# USB_Host.net
KiCad netlist of a schematic drawn in EAGLE
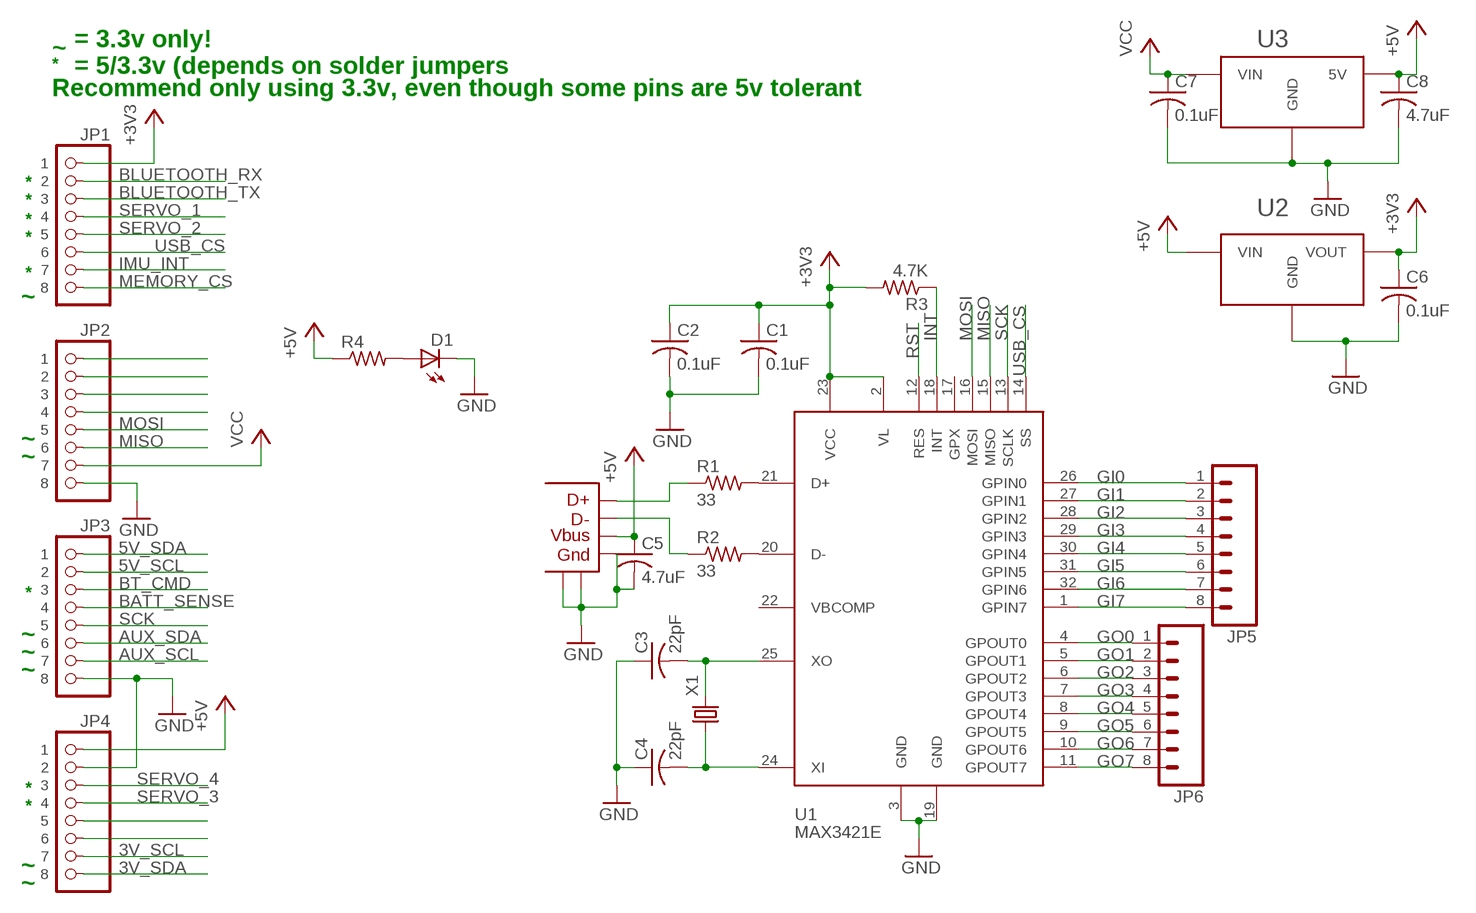
[diagram p0: schematic, sheet 1]

(export (version "E")
  (design (tool "Eeschema 10.0.6"))
  (components
    (comp (ref "C1")
      (value "0.1uF")
      (footprint "eagle-import:C0603")
      (libsource (lib "eagle-import") (part "C-USC0603"))
    )
    (comp (ref "C2")
      (value "0.1uF")
      (footprint "eagle-import:C0603")
      (libsource (lib "eagle-import") (part "C-USC0603"))
    )
    (comp (ref "C3")
      (value "22pF")
      (footprint "eagle-import:C0603")
      (libsource (lib "eagle-import") (part "C-USC0603"))
    )
    (comp (ref "C4")
      (value "22pF")
      (footprint "eagle-import:C0603")
      (libsource (lib "eagle-import") (part "C-USC0603"))
    )
    (comp (ref "C5")
      (value "4.7uF")
      (footprint "eagle-import:C0603")
      (libsource (lib "eagle-import") (part "C-USC0603"))
    )
    (comp (ref "C6")
      (value "0.1uF")
      (footprint "eagle-import:C0603")
      (libsource (lib "eagle-import") (part "C-USC0603"))
    )
    (comp (ref "C7")
      (value "0.1uF")
      (footprint "eagle-import:C0603")
      (libsource (lib "eagle-import") (part "C-USC0603"))
    )
    (comp (ref "C8")
      (value "4.7uF")
      (footprint "eagle-import:C0603")
      (libsource (lib "eagle-import") (part "C-USC0603"))
    )
    (comp (ref "D1")
      (value "LED-GREENLED-0805_NO_SILK")
      (footprint "eagle-import:LED-0805")
      (libsource (lib "eagle-import") (part "LED-GREENLED-0805_NO_SILK"))
    )
    (comp (ref "JP1")
      (value "8-PIN_HEADER")
      (footprint "eagle-import:8-PIN_RECEPTACLE_LOCK_NO-SS")
      (libsource (lib "eagle-import") (part "8-PIN_HEADER"))
    )
    (comp (ref "JP2")
      (value "8-PIN_HEADER")
      (footprint "eagle-import:8-PIN_RECEPTACLE_LOCK_NO-SS")
      (libsource (lib "eagle-import") (part "8-PIN_HEADER"))
    )
    (comp (ref "JP3")
      (value "8-PIN_HEADER")
      (footprint "eagle-import:8-PIN_RECEPTACLE_LOCK_NO-SS")
      (libsource (lib "eagle-import") (part "8-PIN_HEADER"))
    )
    (comp (ref "JP4")
      (value "8-PIN_HEADER")
      (footprint "eagle-import:8-PIN_RECEPTACLE_LOCK_NO-SS")
      (libsource (lib "eagle-import") (part "8-PIN_HEADER"))
    )
    (comp (ref "JP5")
      (value "M081X08")
      (footprint "eagle-import:1X08")
      (libsource (lib "eagle-import") (part "M081X08"))
    )
    (comp (ref "JP6")
      (value "M081X08")
      (footprint "eagle-import:1X08")
      (libsource (lib "eagle-import") (part "M081X08"))
    )
    (comp (ref "R1")
      (value "33")
      (footprint "eagle-import:R0603")
      (libsource (lib "eagle-import") (part "R-US_R0603"))
    )
    (comp (ref "R2")
      (value "33")
      (footprint "eagle-import:R0603")
      (libsource (lib "eagle-import") (part "R-US_R0603"))
    )
    (comp (ref "R3")
      (value "4.7K")
      (footprint "eagle-import:R0603")
      (libsource (lib "eagle-import") (part "R-US_R0603"))
    )
    (comp (ref "R4")
      (value "R-US_R0603")
      (footprint "eagle-import:R0603")
      (libsource (lib "eagle-import") (part "R-US_R0603"))
    )
    (comp (ref "U$1")
      (value "USB_SOCKETTYPE-A")
      (footprint "eagle-import:USB_SOCKET")
      (fields (field (name "PART#") "USB-A1HSW6"))
      (libsource (lib "eagle-import") (part "USB_SOCKETTYPE-A"))
    )
    (comp (ref "U1")
      (value "MAX3421E")
      (footprint "eagle-import:TQFP32_8MIL")
      (libsource (lib "eagle-import") (part "MAX3421E"))
    )
    (comp (ref "U2")
      (value "AP7313SOT23R")
      (footprint "eagle-import:SOT23")
      (libsource (lib "eagle-import") (part "AP7313SOT23R"))
    )
    (comp (ref "U3")
      (value "LM2931")
      (footprint "eagle-import:TO263")
      (libsource (lib "eagle-import") (part "LM2931"))
    )
    (comp (ref "X1")
      (value "CRYSTALTXC-7A")
      (footprint "eagle-import:CRYSTAL-TXC-7A")
      (fields (field (name "PART#") "7A-12.000MAAE-T"))
      (libsource (lib "eagle-import") (part "CRYSTALTXC-7A"))
    )
  )
  (nets
    (net (code "1") (name "+3V3") (class "Default")
      (node (ref "C1") (pin "1") (pinfunction "1_1") (pintype "passive"))
      (node (ref "C2") (pin "1") (pinfunction "1_1") (pintype "passive"))
      (node (ref "C6") (pin "1") (pinfunction "1_1") (pintype "passive"))
      (node (ref "JP1") (pin "P$1") (pinfunction "1_P$1") (pintype "passive"))
      (node (ref "R3") (pin "2") (pinfunction "2_2") (pintype "passive"))
      (node (ref "U1") (pin "2") (pinfunction "VL_2") (pintype "input"))
      (node (ref "U1") (pin "23") (pinfunction "VCC_23") (pintype "power_in"))
      (node (ref "U2") (pin "P$2") (pinfunction "VOUT_P$2") (pintype "bidirectional"))
    )
    (net (code "2") (name "+5V") (class "Default")
      (node (ref "C5") (pin "1") (pinfunction "1_1") (pintype "passive"))
      (node (ref "C8") (pin "1") (pinfunction "1_1") (pintype "passive"))
      (node (ref "JP4") (pin "P$1") (pinfunction "1_P$1") (pintype "passive"))
      (node (ref "R4") (pin "1") (pinfunction "1_1") (pintype "passive"))
      (node (ref "U$1") (pin "P$1") (pinfunction "VBUS_P$1") (pintype "bidirectional"))
      (node (ref "U2") (pin "P$3") (pinfunction "VIN_P$3") (pintype "bidirectional"))
      (node (ref "U3") (pin "P$3") (pinfunction "5V_P$3") (pintype "bidirectional"))
    )
    (net (code "3") (name "/3V_SCL") (class "Default")
      (node (ref "JP4") (pin "P$7") (pinfunction "7_P$7") (pintype "passive"))
    )
    (net (code "4") (name "/3V_SDA") (class "Default")
      (node (ref "JP4") (pin "P$8") (pinfunction "8_P$8") (pintype "passive"))
    )
    (net (code "5") (name "/5V_SCL") (class "Default")
      (node (ref "JP3") (pin "P$2") (pinfunction "2_P$2") (pintype "passive"))
    )
    (net (code "6") (name "/5V_SDA") (class "Default")
      (node (ref "JP3") (pin "P$1") (pinfunction "1_P$1") (pintype "passive"))
    )
    (net (code "7") (name "/AUX_SCL") (class "Default")
      (node (ref "JP3") (pin "P$7") (pinfunction "7_P$7") (pintype "passive"))
    )
    (net (code "8") (name "/AUX_SDA") (class "Default")
      (node (ref "JP3") (pin "P$6") (pinfunction "6_P$6") (pintype "passive"))
    )
    (net (code "9") (name "/BATT_SENSE") (class "Default")
      (node (ref "JP3") (pin "P$4") (pinfunction "4_P$4") (pintype "passive"))
    )
    (net (code "10") (name "/BLUETOOTH_RX") (class "Default")
      (node (ref "JP1") (pin "P$2") (pinfunction "2_P$2") (pintype "passive"))
    )
    (net (code "11") (name "/BLUETOOTH_TX") (class "Default")
      (node (ref "JP1") (pin "P$3") (pinfunction "3_P$3") (pintype "passive"))
    )
    (net (code "12") (name "/BT_CMD") (class "Default")
      (node (ref "JP3") (pin "P$3") (pinfunction "3_P$3") (pintype "passive"))
    )
    (net (code "13") (name "/GI0") (class "Default")
      (node (ref "JP5") (pin "1") (pinfunction "1_1") (pintype "passive"))
      (node (ref "U1") (pin "26") (pinfunction "GPIN0_26") (pintype "input"))
    )
    (net (code "14") (name "/GI1") (class "Default")
      (node (ref "JP5") (pin "2") (pinfunction "2_2") (pintype "passive"))
      (node (ref "U1") (pin "27") (pinfunction "GPIN1_27") (pintype "input"))
    )
    (net (code "15") (name "/GI2") (class "Default")
      (node (ref "JP5") (pin "3") (pinfunction "3_3") (pintype "passive"))
      (node (ref "U1") (pin "28") (pinfunction "GPIN2_28") (pintype "input"))
    )
    (net (code "16") (name "/GI3") (class "Default")
      (node (ref "JP5") (pin "4") (pinfunction "4_4") (pintype "passive"))
      (node (ref "U1") (pin "29") (pinfunction "GPIN3_29") (pintype "input"))
    )
    (net (code "17") (name "/GI4") (class "Default")
      (node (ref "JP5") (pin "5") (pinfunction "5_5") (pintype "passive"))
      (node (ref "U1") (pin "30") (pinfunction "GPIN4_30") (pintype "input"))
    )
    (net (code "18") (name "/GI5") (class "Default")
      (node (ref "JP5") (pin "6") (pinfunction "6_6") (pintype "passive"))
      (node (ref "U1") (pin "31") (pinfunction "GPIN5_31") (pintype "input"))
    )
    (net (code "19") (name "/GI6") (class "Default")
      (node (ref "JP5") (pin "7") (pinfunction "7_7") (pintype "passive"))
      (node (ref "U1") (pin "32") (pinfunction "GPIN6_32") (pintype "input"))
    )
    (net (code "20") (name "/GI7") (class "Default")
      (node (ref "JP5") (pin "8") (pinfunction "8_8") (pintype "passive"))
      (node (ref "U1") (pin "1") (pinfunction "GPIN7_1") (pintype "input"))
    )
    (net (code "21") (name "/GO0") (class "Default")
      (node (ref "JP6") (pin "1") (pinfunction "1_1") (pintype "passive"))
      (node (ref "U1") (pin "4") (pinfunction "GPOUT0_4") (pintype "output"))
    )
    (net (code "22") (name "/GO1") (class "Default")
      (node (ref "JP6") (pin "2") (pinfunction "2_2") (pintype "passive"))
      (node (ref "U1") (pin "5") (pinfunction "GPOUT1_5") (pintype "output"))
    )
    (net (code "23") (name "/GO2") (class "Default")
      (node (ref "JP6") (pin "3") (pinfunction "3_3") (pintype "passive"))
      (node (ref "U1") (pin "6") (pinfunction "GPOUT2_6") (pintype "output"))
    )
    (net (code "24") (name "/GO3") (class "Default")
      (node (ref "JP6") (pin "4") (pinfunction "4_4") (pintype "passive"))
      (node (ref "U1") (pin "7") (pinfunction "GPOUT3_7") (pintype "output"))
    )
    (net (code "25") (name "/GO4") (class "Default")
      (node (ref "JP6") (pin "5") (pinfunction "5_5") (pintype "passive"))
      (node (ref "U1") (pin "8") (pinfunction "GPOUT4_8") (pintype "output"))
    )
    (net (code "26") (name "/GO5") (class "Default")
      (node (ref "JP6") (pin "6") (pinfunction "6_6") (pintype "passive"))
      (node (ref "U1") (pin "9") (pinfunction "GPOUT5_9") (pintype "output"))
    )
    (net (code "27") (name "/GO6") (class "Default")
      (node (ref "JP6") (pin "7") (pinfunction "7_7") (pintype "passive"))
      (node (ref "U1") (pin "10") (pinfunction "GPOUT6_10") (pintype "output"))
    )
    (net (code "28") (name "/GO7") (class "Default")
      (node (ref "JP6") (pin "8") (pinfunction "8_8") (pintype "passive"))
      (node (ref "U1") (pin "11") (pinfunction "GPOUT7_11") (pintype "output"))
    )
    (net (code "29") (name "/IMU_INT") (class "Default")
      (node (ref "JP1") (pin "P$7") (pinfunction "7_P$7") (pintype "passive"))
    )
    (net (code "30") (name "/INT") (class "Default")
      (node (ref "R3") (pin "1") (pinfunction "1_1") (pintype "passive"))
      (node (ref "U1") (pin "18") (pinfunction "INT_18") (pintype "output"))
    )
    (net (code "31") (name "/MEMORY_CS") (class "Default")
      (node (ref "JP1") (pin "P$8") (pinfunction "8_P$8") (pintype "passive"))
    )
    (net (code "32") (name "/MISO") (class "Default")
      (node (ref "JP2") (pin "P$6") (pinfunction "6_P$6") (pintype "passive"))
      (node (ref "U1") (pin "15") (pinfunction "MISO_15") (pintype "output"))
    )
    (net (code "33") (name "/MOSI") (class "Default")
      (node (ref "JP2") (pin "P$5") (pinfunction "5_P$5") (pintype "passive"))
      (node (ref "U1") (pin "16") (pinfunction "MOSI_16") (pintype "input"))
    )
    (net (code "34") (name "/RST") (class "Default")
      (node (ref "U1") (pin "12") (pinfunction "RES_12") (pintype "input"))
    )
    (net (code "35") (name "/SCK") (class "Default")
      (node (ref "JP3") (pin "P$5") (pinfunction "5_P$5") (pintype "passive"))
      (node (ref "U1") (pin "13") (pinfunction "SCLK_13") (pintype "input"))
    )
    (net (code "36") (name "/SERVO_1") (class "Default")
      (node (ref "JP1") (pin "P$4") (pinfunction "4_P$4") (pintype "passive"))
    )
    (net (code "37") (name "/SERVO_2") (class "Default")
      (node (ref "JP1") (pin "P$5") (pinfunction "5_P$5") (pintype "passive"))
    )
    (net (code "38") (name "/SERVO_3") (class "Default")
      (node (ref "JP4") (pin "P$4") (pinfunction "4_P$4") (pintype "passive"))
    )
    (net (code "39") (name "/SERVO_4") (class "Default")
      (node (ref "JP4") (pin "P$3") (pinfunction "3_P$3") (pintype "passive"))
    )
    (net (code "40") (name "/USB_CS") (class "Default")
      (node (ref "JP1") (pin "P$6") (pinfunction "6_P$6") (pintype "passive"))
      (node (ref "U1") (pin "14") (pinfunction "SS_14") (pintype "input"))
    )
    (net (code "41") (name "GND") (class "Default")
      (node (ref "C1") (pin "2") (pinfunction "2_2") (pintype "passive"))
      (node (ref "C2") (pin "2") (pinfunction "2_2") (pintype "passive"))
      (node (ref "C3") (pin "1") (pinfunction "1_1") (pintype "passive"))
      (node (ref "C4") (pin "1") (pinfunction "1_1") (pintype "passive"))
      (node (ref "C5") (pin "2") (pinfunction "2_2") (pintype "passive"))
      (node (ref "C6") (pin "2") (pinfunction "2_2") (pintype "passive"))
      (node (ref "C7") (pin "2") (pinfunction "2_2") (pintype "passive"))
      (node (ref "C8") (pin "2") (pinfunction "2_2") (pintype "passive"))
      (node (ref "D1") (pin "2") (pinfunction "C_2") (pintype "passive"))
      (node (ref "JP2") (pin "P$8") (pinfunction "8_P$8") (pintype "passive"))
      (node (ref "JP3") (pin "P$8") (pinfunction "8_P$8") (pintype "passive"))
      (node (ref "JP4") (pin "P$2") (pinfunction "2_P$2") (pintype "passive"))
      (node (ref "U$1") (pin "P$4") (pinfunction "GND_P$4") (pintype "bidirectional"))
      (node (ref "U$1") (pin "P$5") (pinfunction "P$1_P$5") (pintype "bidirectional"))
      (node (ref "U$1") (pin "P$6") (pinfunction "P$2_P$6") (pintype "bidirectional"))
      (node (ref "U1") (pin "19") (pinfunction "GND_19") (pintype "power_in"))
      (node (ref "U1") (pin "3") (pinfunction "GND_3") (pintype "power_in"))
      (node (ref "U2") (pin "P$1") (pinfunction "GND_P$1") (pintype "bidirectional"))
      (node (ref "U3") (pin "P$1") (pinfunction "GND_P$1") (pintype "bidirectional"))
    )
    (net (code "42") (name "Net-(D1-A)") (class "Default")
      (node (ref "D1") (pin "1") (pinfunction "A_1") (pintype "passive"))
      (node (ref "R4") (pin "2") (pinfunction "2_2") (pintype "passive"))
    )
    (net (code "43") (name "Net-(U$1-D+)") (class "Default")
      (node (ref "R1") (pin "1") (pinfunction "1_1") (pintype "passive"))
      (node (ref "U$1") (pin "P$3") (pinfunction "D+_P$3") (pintype "bidirectional"))
    )
    (net (code "44") (name "Net-(U$1-D-)") (class "Default")
      (node (ref "R2") (pin "1") (pinfunction "1_1") (pintype "passive"))
      (node (ref "U$1") (pin "P$2") (pinfunction "D-_P$2") (pintype "bidirectional"))
    )
    (net (code "45") (name "Net-(U1-D+)") (class "Default")
      (node (ref "R1") (pin "2") (pinfunction "2_2") (pintype "passive"))
      (node (ref "U1") (pin "21") (pinfunction "D+_21") (pintype "bidirectional"))
    )
    (net (code "46") (name "Net-(U1-D-)") (class "Default")
      (node (ref "R2") (pin "2") (pinfunction "2_2") (pintype "passive"))
      (node (ref "U1") (pin "20") (pinfunction "D-_20") (pintype "bidirectional"))
    )
    (net (code "47") (name "Net-(U1-XI)") (class "Default")
      (node (ref "C4") (pin "2") (pinfunction "2_2") (pintype "passive"))
      (node (ref "U1") (pin "24") (pinfunction "XI_24") (pintype "input"))
      (node (ref "X1") (pin "P$1") (pinfunction "1_P$1") (pintype "passive"))
    )
    (net (code "48") (name "Net-(U1-XO)") (class "Default")
      (node (ref "C3") (pin "2") (pinfunction "2_2") (pintype "passive"))
      (node (ref "U1") (pin "25") (pinfunction "XO_25") (pintype "output"))
      (node (ref "X1") (pin "P$2") (pinfunction "2_P$2") (pintype "passive"))
    )
    (net (code "49") (name "VCC") (class "Default")
      (node (ref "C7") (pin "1") (pinfunction "1_1") (pintype "passive"))
      (node (ref "JP2") (pin "P$7") (pinfunction "7_P$7") (pintype "passive"))
      (node (ref "U3") (pin "P$2") (pinfunction "VIN_P$2") (pintype "bidirectional"))
    )
    (net (code "50") (name "unconnected-(JP2-1-PadP$1)") (class "Default")
      (node (ref "JP2") (pin "P$1") (pinfunction "1_P$1") (pintype "passive"))
    )
    (net (code "51") (name "unconnected-(JP2-2-PadP$2)") (class "Default")
      (node (ref "JP2") (pin "P$2") (pinfunction "2_P$2") (pintype "passive"))
    )
    (net (code "52") (name "unconnected-(JP2-3-PadP$3)") (class "Default")
      (node (ref "JP2") (pin "P$3") (pinfunction "3_P$3") (pintype "passive"))
    )
    (net (code "53") (name "unconnected-(JP2-4-PadP$4)") (class "Default")
      (node (ref "JP2") (pin "P$4") (pinfunction "4_P$4") (pintype "passive"))
    )
    (net (code "54") (name "unconnected-(JP4-5-PadP$5)") (class "Default")
      (node (ref "JP4") (pin "P$5") (pinfunction "5_P$5") (pintype "passive"))
    )
    (net (code "55") (name "unconnected-(JP4-6-PadP$6)") (class "Default")
      (node (ref "JP4") (pin "P$6") (pinfunction "6_P$6") (pintype "passive"))
    )
    (net (code "56") (name "unconnected-(U1-GPX-Pad17)") (class "Default")
      (node (ref "U1") (pin "17") (pinfunction "GPX_17") (pintype "output"))
    )
    (net (code "57") (name "unconnected-(U1-VBCOMP-Pad22)") (class "Default")
      (node (ref "U1") (pin "22") (pinfunction "VBCOMP_22") (pintype "input"))
    )
  )
)
